# IMU.net
KiCad netlist of a schematic drawn in EAGLE
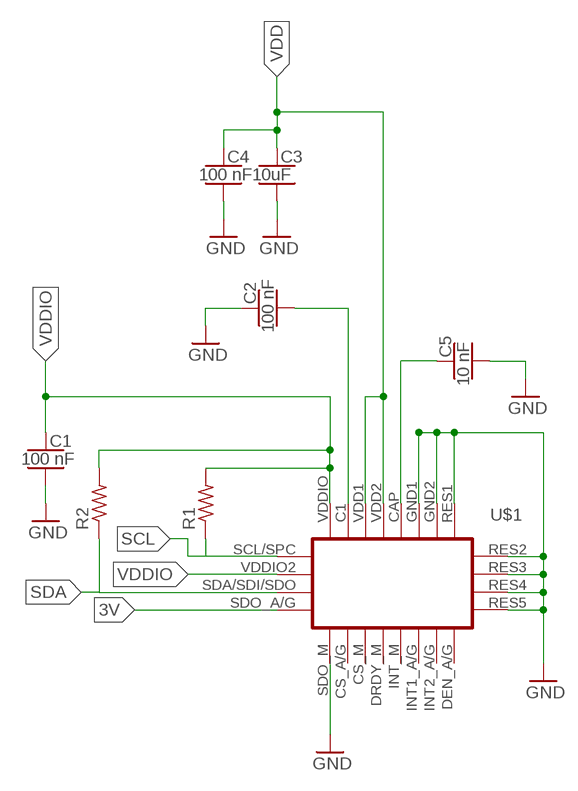
[diagram p0: schematic, sheet 1]

(export (version "E")
  (design (tool "Eeschema 10.0.6"))
  (components
    (comp (ref "C1")
      (value "100 nF")
      (footprint "eagle-import:CAPC2012X140_HS")
      (libsource (lib "eagle-import") (part "CAPACITOR-NP_SMD-2012-0805_CERAMIC"))
    )
    (comp (ref "C2")
      (value "100 nF")
      (footprint "eagle-import:CAPC2012X140_HS")
      (libsource (lib "eagle-import") (part "CAPACITOR-NP_SMD-2012-0805_CERAMIC"))
    )
    (comp (ref "C3")
      (value "10uF")
      (footprint "eagle-import:CAPC2012X140_HS")
      (fields
        (field (name "MFR") "Murata Electronics North America")
        (field (name "MPN") "GRM21BR61E106KA73L")
      )
      (libsource (lib "eagle-import") (part "CAPACITOR-NP_SMD-2012-0805_CERAMIC-10UF"))
    )
    (comp (ref "C4")
      (value "100 nF")
      (footprint "eagle-import:CAPC2012X140_HS")
      (libsource (lib "eagle-import") (part "CAPACITOR-NP_SMD-2012-0805_CERAMIC"))
    )
    (comp (ref "C5")
      (value "10 nF")
      (footprint "eagle-import:CAPC2012X140_HS")
      (libsource (lib "eagle-import") (part "CAPACITOR-NP_SMD-2012-0805_CERAMIC"))
    )
    (comp (ref "R1")
      (value "RESISTOR_SMD-2012-0805")
      (footprint "eagle-import:RESC2012X60_HS")
      (libsource (lib "eagle-import") (part "RESISTOR_SMD-2012-0805"))
    )
    (comp (ref "R2")
      (value "RESISTOR_SMD-2012-0805")
      (footprint "eagle-import:RESC2012X60_HS")
      (libsource (lib "eagle-import") (part "RESISTOR_SMD-2012-0805"))
    )
    (comp (ref "U$1")
      (value "IMU_9AXIS")
      (footprint "eagle-import:IMU_9AXIS")
      (fields
        (field (name "MFR") "STMicroelectronics")
        (field (name "MPN") "LSM9DS1TR")
        (field (name "CREATOR") "Alexander Orr")
      )
      (libsource (lib "eagle-import") (part "IMU_9AXIS"))
    )
  )
  (nets
    (net (code "1") (name "3V") (class "Default")
      (node (ref "U$1") (pin "SDO_A/G") (pinfunction "SDO_A/G_SDO_A/G") (pintype "bidirectional"))
    )
    (net (code "2") (name "GND") (class "Default")
      (node (ref "C1") (pin "2") (pinfunction "2_2") (pintype "passive"))
      (node (ref "C2") (pin "1") (pinfunction "1_1") (pintype "passive"))
      (node (ref "C3") (pin "2") (pinfunction "2_2") (pintype "passive"))
      (node (ref "C4") (pin "2") (pinfunction "2_2") (pintype "passive"))
      (node (ref "C5") (pin "2") (pinfunction "2_2") (pintype "passive"))
      (node (ref "U$1") (pin "GND1") (pinfunction "GND1_GND1") (pintype "power_in"))
      (node (ref "U$1") (pin "GND2") (pinfunction "GND2_GND2") (pintype "power_in"))
      (node (ref "U$1") (pin "RES1") (pinfunction "RES1_RES1") (pintype "passive"))
      (node (ref "U$1") (pin "RES2") (pinfunction "RES2_RES2") (pintype "passive"))
      (node (ref "U$1") (pin "RES3") (pinfunction "RES3_RES3") (pintype "passive"))
      (node (ref "U$1") (pin "RES4") (pinfunction "RES4_RES4") (pintype "passive"))
      (node (ref "U$1") (pin "RES5") (pinfunction "RES5_RES5") (pintype "passive"))
      (node (ref "U$1") (pin "SDO_M") (pinfunction "SDO_M_SDO_M") (pintype "bidirectional"))
    )
    (net (code "3") (name "Net-(C2-Pad2)") (class "Default")
      (node (ref "C2") (pin "2") (pinfunction "2_2") (pintype "passive"))
      (node (ref "U$1") (pin "C1") (pinfunction "C1_C1") (pintype "bidirectional"))
    )
    (net (code "4") (name "Net-(C5-Pad1)") (class "Default")
      (node (ref "C5") (pin "1") (pinfunction "1_1") (pintype "passive"))
      (node (ref "U$1") (pin "CAP") (pinfunction "CAP_CAP") (pintype "passive"))
    )
    (net (code "5") (name "SCL") (class "Default")
      (node (ref "R1") (pin "1") (pinfunction "1_1") (pintype "passive"))
      (node (ref "U$1") (pin "SCL/SPC") (pinfunction "SCL/SPC_SCL/SPC") (pintype "bidirectional"))
    )
    (net (code "6") (name "SDA") (class "Default")
      (node (ref "R2") (pin "1") (pinfunction "1_1") (pintype "passive"))
      (node (ref "U$1") (pin "SDA/SDI/SDO") (pinfunction "SDA/SDI/SDO_SDA/SDI/SDO") (pintype "bidirectional"))
    )
    (net (code "7") (name "VDD") (class "Default")
      (node (ref "C3") (pin "1") (pinfunction "1_1") (pintype "passive"))
      (node (ref "C4") (pin "1") (pinfunction "1_1") (pintype "passive"))
      (node (ref "U$1") (pin "VDD1") (pinfunction "VDD1_VDD1") (pintype "power_in"))
      (node (ref "U$1") (pin "VDD2") (pinfunction "VDD2_VDD2") (pintype "power_in"))
    )
    (net (code "8") (name "VDDIO") (class "Default")
      (node (ref "C1") (pin "1") (pinfunction "1_1") (pintype "passive"))
      (node (ref "R1") (pin "2") (pinfunction "2_2") (pintype "passive"))
      (node (ref "R2") (pin "2") (pinfunction "2_2") (pintype "passive"))
      (node (ref "U$1") (pin "VDDIO") (pinfunction "VDDIO1_VDDIO") (pintype "bidirectional"))
      (node (ref "U$1") (pin "VDDIO2") (pinfunction "VDDIO2_VDDIO2") (pintype "bidirectional"))
    )
    (net (code "9") (name "unconnected-(U$1-PadCS_A{slash}G)") (class "Default")
      (node (ref "U$1") (pin "CS_A/G") (pinfunction "CS_A/G_CS_A/G") (pintype "bidirectional"))
    )
    (net (code "10") (name "unconnected-(U$1-PadCS_M)") (class "Default")
      (node (ref "U$1") (pin "CS_M") (pinfunction "CS_M_CS_M") (pintype "bidirectional"))
    )
    (net (code "11") (name "unconnected-(U$1-PadDEN_A{slash}G)") (class "Default")
      (node (ref "U$1") (pin "DEN_A/G") (pinfunction "DEN_A/G_DEN_A/G") (pintype "bidirectional"))
    )
    (net (code "12") (name "unconnected-(U$1-PadDRDY_M)") (class "Default")
      (node (ref "U$1") (pin "DRDY_M") (pinfunction "DRDY_M_DRDY_M") (pintype "bidirectional"))
    )
    (net (code "13") (name "unconnected-(U$1-PadINT1_A{slash}G)") (class "Default")
      (node (ref "U$1") (pin "INT1_A/G") (pinfunction "INT1_A/G_INT1_A/G") (pintype "bidirectional"))
    )
    (net (code "14") (name "unconnected-(U$1-PadINT2_A{slash}G)") (class "Default")
      (node (ref "U$1") (pin "INT2_A/G") (pinfunction "INT2_A/G_INT2_A/G") (pintype "bidirectional"))
    )
    (net (code "15") (name "unconnected-(U$1-PadINT_M)") (class "Default")
      (node (ref "U$1") (pin "INT_M") (pinfunction "INT_M_INT_M") (pintype "bidirectional"))
    )
  )
)
